# voltage_regulation.net
KiCad netlist of a schematic drawn in Altium Designer
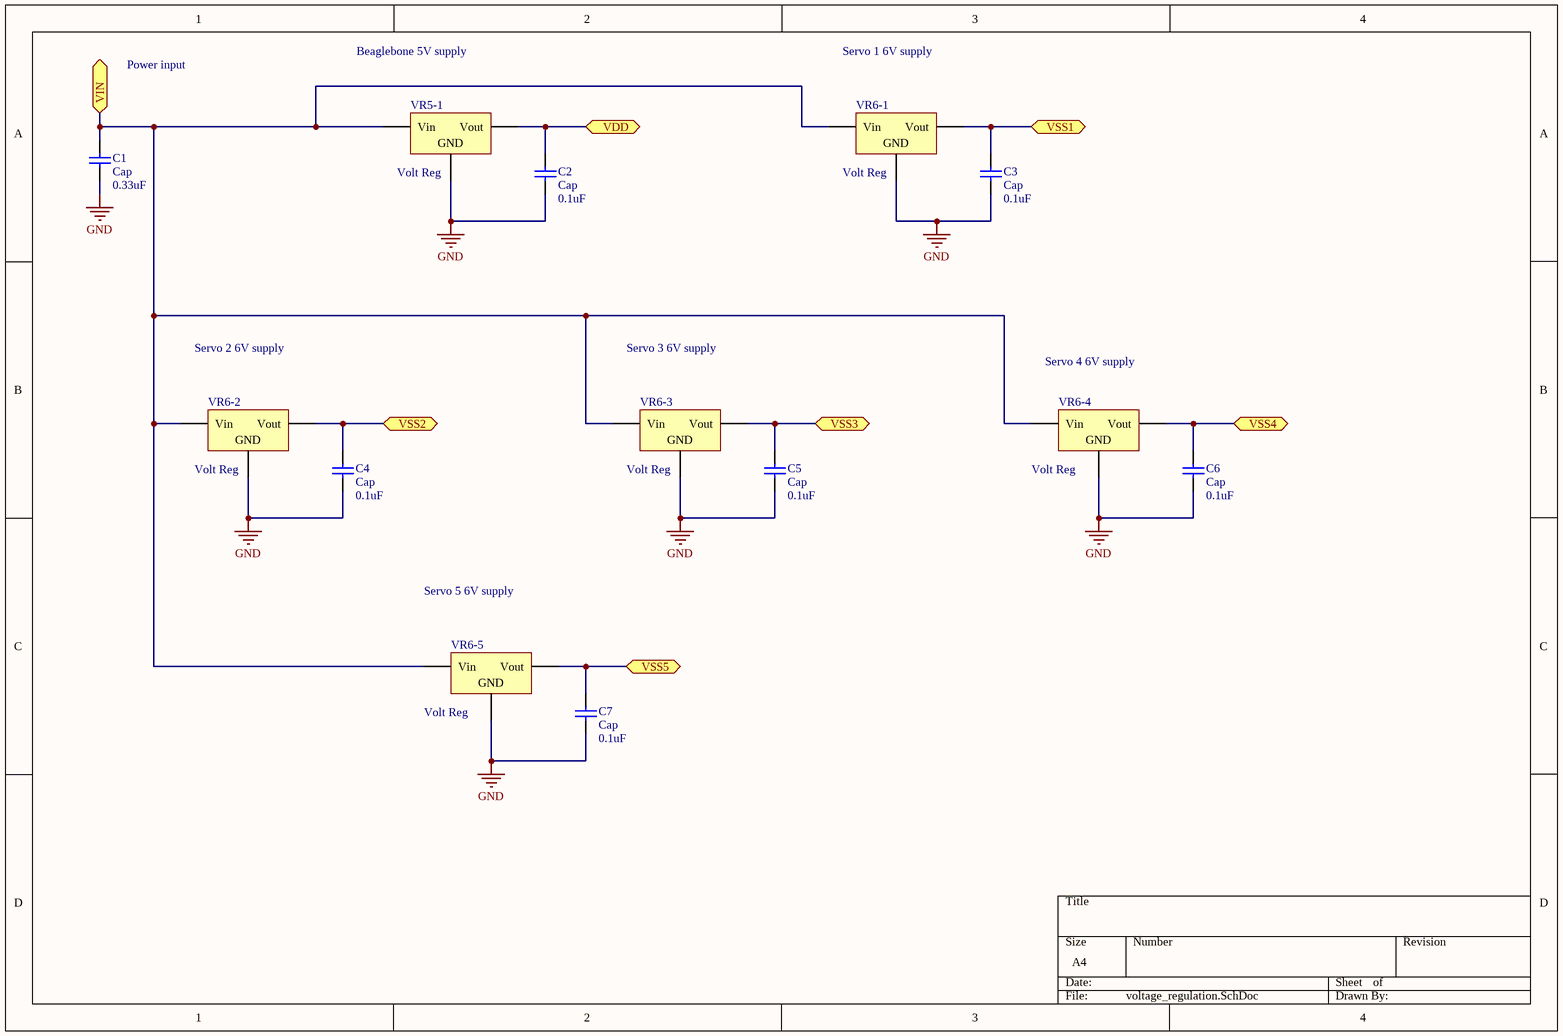
[diagram p0: voltage_regulation.SchDoc]

(export (version "E")
  (design (tool "Eeschema 10.0.6"))
  (components
    (comp (ref "C1")
      (value "Cap")
      (footprint "RAD-0.3")
      (description "Capacitor")
      (fields (field (name "ALTIUM_VALUE") "0.33uF") (field (name "PUBLISHER") "Altium Limited"))
      (libsource (lib "Miscellaneous Devices") (part "Cap"))
    )
    (comp (ref "C2")
      (value "Cap")
      (footprint "RAD-0.3")
      (description "Capacitor")
      (fields (field (name "ALTIUM_VALUE") "0.1uF") (field (name "PUBLISHER") "Altium Limited"))
      (libsource (lib "Miscellaneous Devices") (part "Cap"))
    )
    (comp (ref "C3")
      (value "Cap")
      (footprint "RAD-0.3")
      (description "Capacitor")
      (fields (field (name "ALTIUM_VALUE") "0.1uF") (field (name "PUBLISHER") "Altium Limited"))
      (libsource (lib "Miscellaneous Devices") (part "Cap"))
    )
    (comp (ref "C4")
      (value "Cap")
      (footprint "RAD-0.3")
      (description "Capacitor")
      (fields (field (name "ALTIUM_VALUE") "0.1uF") (field (name "PUBLISHER") "Altium Limited"))
      (libsource (lib "Miscellaneous Devices") (part "Cap"))
    )
    (comp (ref "C5")
      (value "Cap")
      (footprint "RAD-0.3")
      (description "Capacitor")
      (fields (field (name "ALTIUM_VALUE") "0.1uF") (field (name "PUBLISHER") "Altium Limited"))
      (libsource (lib "Miscellaneous Devices") (part "Cap"))
    )
    (comp (ref "C6")
      (value "Cap")
      (footprint "RAD-0.3")
      (description "Capacitor")
      (fields (field (name "ALTIUM_VALUE") "0.1uF") (field (name "PUBLISHER") "Altium Limited"))
      (libsource (lib "Miscellaneous Devices") (part "Cap"))
    )
    (comp (ref "C7")
      (value "Cap")
      (footprint "RAD-0.3")
      (description "Capacitor")
      (fields (field (name "ALTIUM_VALUE") "0.1uF") (field (name "PUBLISHER") "Altium Limited"))
      (libsource (lib "Miscellaneous Devices") (part "Cap"))
    )
    (comp (ref "VR5-1")
      (value "Volt Reg")
      (footprint "D2PAK_N")
      (description "Voltage Regulator")
      (fields (field (name "PUBLISHER") "Altium Limited"))
      (libsource (lib "Miscellaneous Devices") (part "Volt Reg"))
    )
    (comp (ref "VR6-1")
      (value "Volt Reg")
      (footprint "D2PAK_N")
      (description "Voltage Regulator")
      (fields (field (name "PUBLISHER") "Altium Limited"))
      (libsource (lib "Miscellaneous Devices") (part "Volt Reg"))
    )
    (comp (ref "VR6-2")
      (value "Volt Reg")
      (footprint "D2PAK_N")
      (description "Voltage Regulator")
      (fields (field (name "PUBLISHER") "Altium Limited"))
      (libsource (lib "Miscellaneous Devices") (part "Volt Reg"))
    )
    (comp (ref "VR6-3")
      (value "Volt Reg")
      (footprint "D2PAK_N")
      (description "Voltage Regulator")
      (fields (field (name "PUBLISHER") "Altium Limited"))
      (libsource (lib "Miscellaneous Devices") (part "Volt Reg"))
    )
    (comp (ref "VR6-4")
      (value "Volt Reg")
      (footprint "D2PAK_N")
      (description "Voltage Regulator")
      (fields (field (name "PUBLISHER") "Altium Limited"))
      (libsource (lib "Miscellaneous Devices") (part "Volt Reg"))
    )
    (comp (ref "VR6-5")
      (value "Volt Reg")
      (footprint "D2PAK_N")
      (description "Voltage Regulator")
      (fields (field (name "PUBLISHER") "Altium Limited"))
      (libsource (lib "Miscellaneous Devices") (part "Volt Reg"))
    )
  )
  (nets
    (net (code "1") (name "/VDD") (class "Default")
      (node (ref "C2") (pin "2") (pinfunction "2_2") (pintype "passive"))
      (node (ref "VR5-1") (pin "3") (pinfunction "Vout_3") (pintype "passive"))
    )
    (net (code "2") (name "/VIN") (class "Default")
      (node (ref "C1") (pin "2") (pinfunction "2_2") (pintype "passive"))
      (node (ref "VR5-1") (pin "1") (pinfunction "Vin_1") (pintype "passive"))
      (node (ref "VR6-1") (pin "1") (pinfunction "Vin_1") (pintype "passive"))
      (node (ref "VR6-2") (pin "1") (pinfunction "Vin_1") (pintype "passive"))
      (node (ref "VR6-3") (pin "1") (pinfunction "Vin_1") (pintype "passive"))
      (node (ref "VR6-4") (pin "1") (pinfunction "Vin_1") (pintype "passive"))
      (node (ref "VR6-5") (pin "1") (pinfunction "Vin_1") (pintype "passive"))
    )
    (net (code "3") (name "/VSS1") (class "Default")
      (node (ref "C3") (pin "2") (pinfunction "2_2") (pintype "passive"))
      (node (ref "VR6-1") (pin "3") (pinfunction "Vout_3") (pintype "passive"))
    )
    (net (code "4") (name "/VSS2") (class "Default")
      (node (ref "C4") (pin "2") (pinfunction "2_2") (pintype "passive"))
      (node (ref "VR6-2") (pin "3") (pinfunction "Vout_3") (pintype "passive"))
    )
    (net (code "5") (name "/VSS3") (class "Default")
      (node (ref "C5") (pin "2") (pinfunction "2_2") (pintype "passive"))
      (node (ref "VR6-3") (pin "3") (pinfunction "Vout_3") (pintype "passive"))
    )
    (net (code "6") (name "/VSS4") (class "Default")
      (node (ref "C6") (pin "2") (pinfunction "2_2") (pintype "passive"))
      (node (ref "VR6-4") (pin "3") (pinfunction "Vout_3") (pintype "passive"))
    )
    (net (code "7") (name "/VSS5") (class "Default")
      (node (ref "C7") (pin "2") (pinfunction "2_2") (pintype "passive"))
      (node (ref "VR6-5") (pin "3") (pinfunction "Vout_3") (pintype "passive"))
    )
    (net (code "8") (name "GND") (class "Default")
      (node (ref "C1") (pin "1") (pinfunction "1_1") (pintype "passive"))
      (node (ref "C2") (pin "1") (pinfunction "1_1") (pintype "passive"))
      (node (ref "C3") (pin "1") (pinfunction "1_1") (pintype "passive"))
      (node (ref "C4") (pin "1") (pinfunction "1_1") (pintype "passive"))
      (node (ref "C5") (pin "1") (pinfunction "1_1") (pintype "passive"))
      (node (ref "C6") (pin "1") (pinfunction "1_1") (pintype "passive"))
      (node (ref "C7") (pin "1") (pinfunction "1_1") (pintype "passive"))
      (node (ref "VR5-1") (pin "2") (pinfunction "GND_2") (pintype "passive"))
      (node (ref "VR6-1") (pin "2") (pinfunction "GND_2") (pintype "passive"))
      (node (ref "VR6-2") (pin "2") (pinfunction "GND_2") (pintype "passive"))
      (node (ref "VR6-3") (pin "2") (pinfunction "GND_2") (pintype "passive"))
      (node (ref "VR6-4") (pin "2") (pinfunction "GND_2") (pintype "passive"))
      (node (ref "VR6-5") (pin "2") (pinfunction "GND_2") (pintype "passive"))
    )
  )
)
